# CAN0.net
KiCad netlist of a schematic drawn in Altium Designer
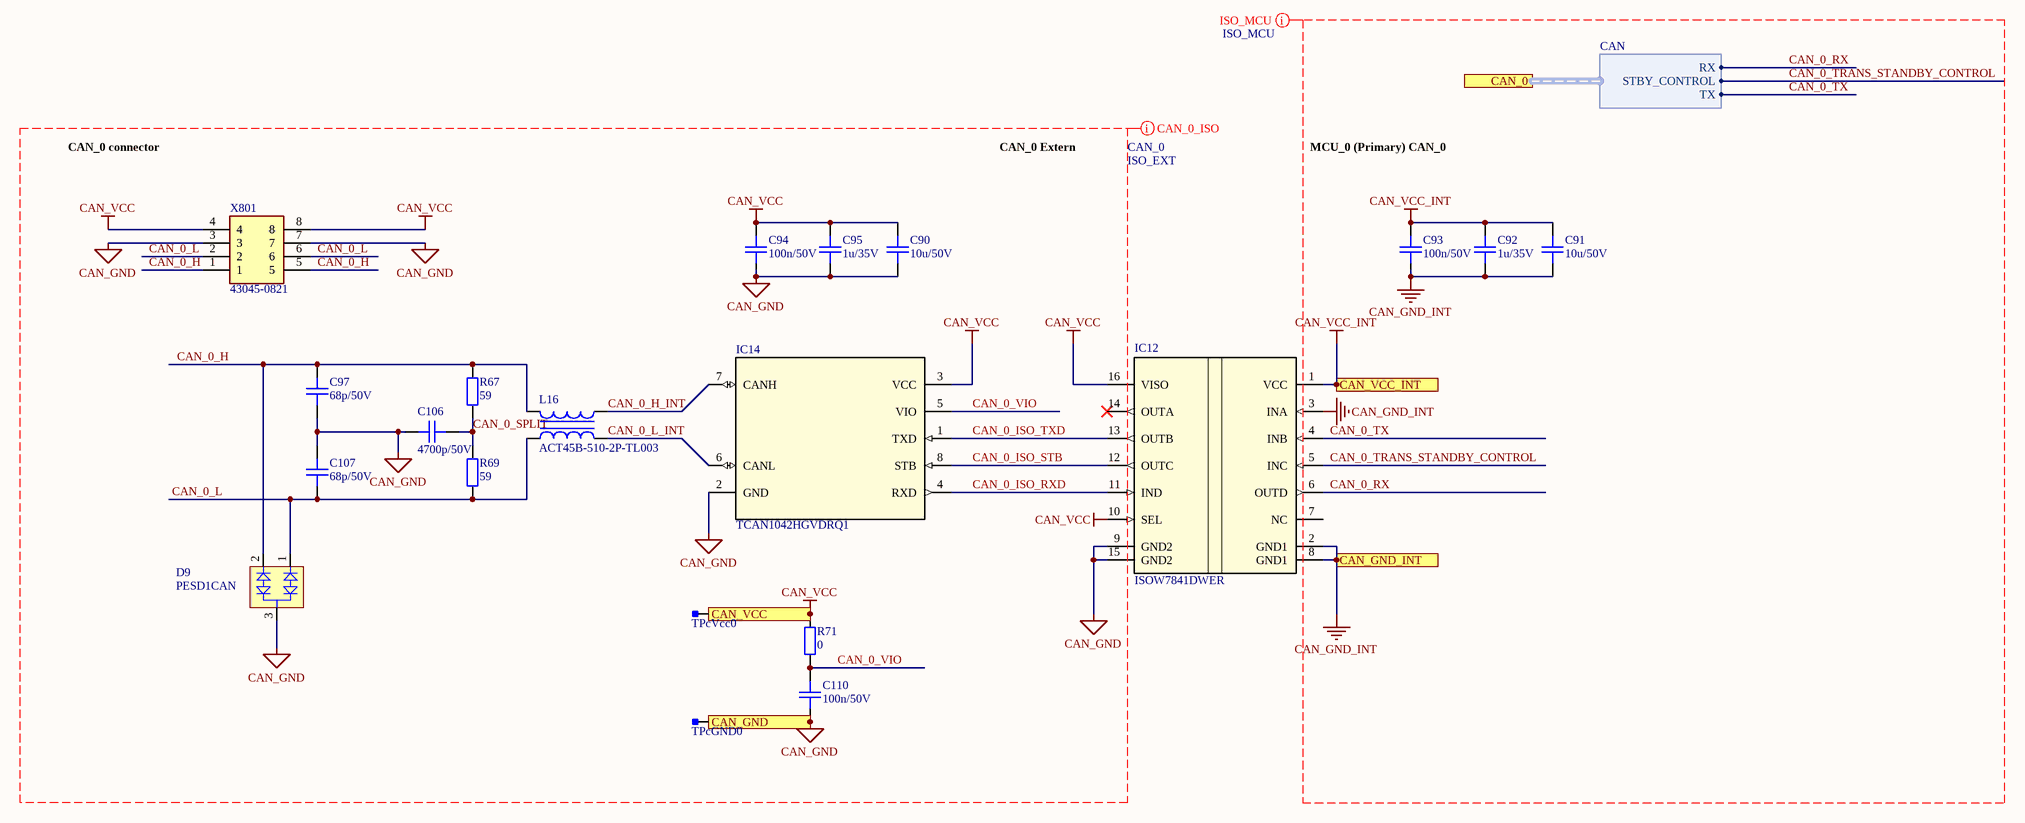
[diagram p0: CAN0.SchDoc]

(export (version "E")
  (design (tool "Eeschema 10.0.6"))
  (components
    (comp (ref "C90")
      (value "10u/50V")
      (footprint "0805C")
      (description "MLCC")
      (fields (field (name "PART NUMBER") "gen_C_ceramic_2u2_50V_X7R_0805"))
      (libsource (lib "OE750") (part "C"))
    )
    (comp (ref "C91")
      (value "10u/50V")
      (footprint "0805C")
      (description "MLCC")
      (fields (field (name "PART NUMBER") "gen_C_ceramic_2u2_50V_X7R_0805"))
      (libsource (lib "OE750") (part "C"))
    )
    (comp (ref "C92")
      (value "1u/35V")
      (footprint "0603C")
      (description "MLCC")
      (fields (field (name "PART NUMBER") "gen_C_ceramic_1u_35V_X7R_0603"))
      (libsource (lib "OE750") (part "C"))
    )
    (comp (ref "C93")
      (value "100n/50V")
      (footprint "0603C")
      (description "MLCC")
      (fields (field (name "PART NUMBER") "gen_C_ceramic_100n_50V_X7R_0603"))
      (libsource (lib "OE750") (part "C"))
    )
    (comp (ref "C94")
      (value "100n/50V")
      (footprint "0603C")
      (description "MLCC")
      (fields (field (name "PART NUMBER") "gen_C_ceramic_100n_50V_X7R_0603"))
      (libsource (lib "OE750") (part "C"))
    )
    (comp (ref "C95")
      (value "1u/35V")
      (footprint "0603C")
      (description "MLCC")
      (fields (field (name "PART NUMBER") "gen_C_ceramic_1u_35V_X7R_0603"))
      (libsource (lib "OE750") (part "C"))
    )
    (comp (ref "C97")
      (value "68p/50V")
      (footprint "0603C")
      (description "MLCC")
      (fields (field (name "PART NUMBER") "gen_C_ceramic_4n7_50V_X7R_0603"))
      (libsource (lib "OE750") (part "C"))
    )
    (comp (ref "C106")
      (value "4700p/50V")
      (footprint "0603C")
      (description "MLCC")
      (libsource (lib "OE750") (part "C"))
    )
    (comp (ref "C107")
      (value "68p/50V")
      (footprint "0603C")
      (description "MLCC")
      (fields (field (name "PART NUMBER") "gen_C_ceramic_4n7_50V_X7R_0603"))
      (libsource (lib "OE750") (part "C"))
    )
    (comp (ref "C110")
      (value "100n/50V")
      (footprint "0603C")
      (description "MLCC")
      (fields (field (name "PART NUMBER") "gen_C_ceramic_100n_50V_X7R_0603"))
      (libsource (lib "OE750") (part "C"))
    )
    (comp (ref "D9")
      (value "PESD1CAN")
      (footprint "NXP-SOT23-3_V")
      (description "CAN Bus ESD Protection Diode, 200 W, 24 V, -65 to 150 degC, 3-Pin SOT23, RoHS, Tape and Reel")
      (fields (field (name "MANUFACTURER") "NXP Semiconductors"))
      (libsource (lib "Altium Content Vault") (part "NXP-PESD1CAN-SOT23-3"))
    )
    (comp (ref "IC12")
      (value "ISOW7841DWER")
      (footprint "DWE0016A")
      (description "Imported")
      (fields (field (name "MANUFACTURER") "Texas Instruments"))
      (libsource (lib "ti-import") (part "ISOW7841DWER"))
    )
    (comp (ref "IC14")
      (value "TCAN1042HGVDRQ1")
      (footprint "D0008A_N")
      (description "Imported")
      (fields (field (name "PARTNUMBER") "TCAN1042HGVDQ1") (field (name "MANUFACTURER") "Texas Instruments"))
      (libsource (lib "ti-import") (part "TCAN1042HGVDRQ1"))
    )
    (comp (ref "L16")
      (value "ACT45B-510-2P-TL003")
      (footprint "TDK-ACT45B-510-2P-TL003-4_V")
      (fields (field (name "MANUFACTURER") "TDK"))
      (libsource (lib "Altium Content Vault") (part "TDK-ACXXXXX-XXX-2P-T000-4"))
    )
    (comp (ref "R67")
      (value "59")
      (footprint "0805R")
      (description "SMD Resistor 62R 0603")
      (fields (field (name "PART NUMBER") "gen_R_62R_0603") (field (name "TOLERANCE") "1%"))
      (libsource (lib "OE750") (part "R"))
    )
    (comp (ref "R69")
      (value "59")
      (footprint "0805R")
      (description "SMD Resistor 62R 0603")
      (fields (field (name "PART NUMBER") "gen_R_62R_0603") (field (name "TOLERANCE") "1%"))
      (libsource (lib "OE750") (part "R"))
    )
    (comp (ref "R71")
      (value "0")
      (footprint "0603R")
      (description "SMD Resistor 430R 0603")
      (fields (field (name "PART NUMBER") "gen_R_430R_0603") (field (name "TOLERANCE") "1%"))
      (libsource (lib "OE750") (part "R"))
    )
    (comp (ref "TPcGND0")
      (value "Testpoint_Square")
      (footprint "Testpoint_S1")
      (description "Testpoint, square")
      (libsource (lib "OE750") (part "Testpoint_Square"))
    )
    (comp (ref "TPcVcc0")
      (value "Testpoint_Square")
      (footprint "Testpoint_S1")
      (description "Testpoint, square")
      (libsource (lib "OE750") (part "Testpoint_Square"))
    )
    (comp (ref "X801")
      (value "43045-0821")
      (footprint "43045-0821")
      (description "Connector")
      (fields (field (name "MOUSER PART NUMBER") "538-43045-0821"))
      (libsource (lib "SamacSys") (part "43045-0821"))
    )
  )
  (nets
    (net (code "2") (name "/CAN_0_H") (class "Default")
      (node (ref "C97") (pin "2") (pinfunction "2_2") (pintype "passive"))
      (node (ref "D9") (pin "2") (pinfunction "K2_2") (pintype "passive"))
      (node (ref "L16") (pin "2") (pinfunction "2_2") (pintype "passive"))
      (node (ref "R67") (pin "2") (pinfunction "2_2") (pintype "passive"))
      (node (ref "X801") (pin "1") (pinfunction "1_1") (pintype "passive"))
      (node (ref "X801") (pin "5") (pinfunction "5_5") (pintype "passive"))
    )
    (net (code "3") (name "/CAN_0_H_INT") (class "Default")
      (node (ref "IC14") (pin "7") (pinfunction "CANH_7") (pintype "bidirectional"))
      (node (ref "L16") (pin "3") (pinfunction "3_3") (pintype "passive"))
    )
    (net (code "4") (name "/CAN_0_ISO_RXD") (class "Default")
      (node (ref "IC12") (pin "11") (pinfunction "IND_11") (pintype "input"))
      (node (ref "IC14") (pin "4") (pinfunction "RXD_4") (pintype "output"))
    )
    (net (code "5") (name "/CAN_0_ISO_STB") (class "Default")
      (node (ref "IC12") (pin "12") (pinfunction "OUTC_12") (pintype "output"))
      (node (ref "IC14") (pin "8") (pinfunction "STB_8") (pintype "input"))
    )
    (net (code "6") (name "/CAN_0_ISO_TXD") (class "Default")
      (node (ref "IC12") (pin "13") (pinfunction "OUTB_13") (pintype "output"))
      (node (ref "IC14") (pin "1") (pinfunction "TXD_1") (pintype "input"))
    )
    (net (code "7") (name "/CAN_0_L") (class "Default")
      (node (ref "C107") (pin "1") (pinfunction "1_1") (pintype "passive"))
      (node (ref "D9") (pin "1") (pinfunction "K1_1") (pintype "passive"))
      (node (ref "L16") (pin "1") (pinfunction "1_1") (pintype "passive"))
      (node (ref "R69") (pin "1") (pinfunction "1_1") (pintype "passive"))
      (node (ref "X801") (pin "2") (pinfunction "2_2") (pintype "passive"))
      (node (ref "X801") (pin "6") (pinfunction "6_6") (pintype "passive"))
    )
    (net (code "8") (name "/CAN_0_L_INT") (class "Default")
      (node (ref "IC14") (pin "6") (pinfunction "CANL_6") (pintype "bidirectional"))
      (node (ref "L16") (pin "4") (pinfunction "4_4") (pintype "passive"))
    )
    (net (code "9") (name "/CAN_0_RX") (class "Default")
      (node (ref "IC12") (pin "6") (pinfunction "OUTD_6") (pintype "output"))
    )
    (net (code "10") (name "/CAN_0_SPLIT") (class "Default")
      (node (ref "C106") (pin "2") (pinfunction "2_2") (pintype "passive"))
      (node (ref "R67") (pin "1") (pinfunction "1_1") (pintype "passive"))
      (node (ref "R69") (pin "2") (pinfunction "2_2") (pintype "passive"))
    )
    (net (code "11") (name "/CAN_0_TRANS_STANDBY_CONTROL") (class "Default")
      (node (ref "IC12") (pin "5") (pinfunction "INC_5") (pintype "input"))
    )
    (net (code "12") (name "/CAN_0_TX") (class "Default")
      (node (ref "IC12") (pin "4") (pinfunction "INB_4") (pintype "input"))
    )
    (net (code "13") (name "/CAN_0_VIO") (class "Default")
      (node (ref "C110") (pin "2") (pinfunction "2_2") (pintype "passive"))
      (node (ref "IC14") (pin "5") (pinfunction "VIO_5") (pintype "power_in"))
      (node (ref "R71") (pin "2") (pinfunction "2_2") (pintype "passive"))
    )
    (net (code "15") (name "CAN_GND") (class "Default")
      (node (ref "C106") (pin "1") (pinfunction "1_1") (pintype "passive"))
      (node (ref "C107") (pin "2") (pinfunction "2_2") (pintype "passive"))
      (node (ref "C110") (pin "1") (pinfunction "1_1") (pintype "passive"))
      (node (ref "C90") (pin "2") (pinfunction "2_2") (pintype "passive"))
      (node (ref "C94") (pin "1") (pinfunction "1_1") (pintype "passive"))
      (node (ref "C95") (pin "1") (pinfunction "1_1") (pintype "passive"))
      (node (ref "C97") (pin "1") (pinfunction "1_1") (pintype "passive"))
      (node (ref "D9") (pin "3") (pinfunction "C_3") (pintype "passive"))
      (node (ref "IC12") (pin "15") (pinfunction "GND2_15") (pintype "power_in"))
      (node (ref "IC12") (pin "9") (pinfunction "GND2_9") (pintype "power_in"))
      (node (ref "IC14") (pin "2") (pinfunction "GND_2") (pintype "power_in"))
      (node (ref "TPcGND0") (pin "1") (pinfunction "1_1") (pintype "passive"))
      (node (ref "X801") (pin "3") (pinfunction "3_3") (pintype "passive"))
      (node (ref "X801") (pin "7") (pinfunction "7_7") (pintype "passive"))
    )
    (net (code "16") (name "CAN_GND_INT") (class "Default")
      (node (ref "C91") (pin "2") (pinfunction "2_2") (pintype "passive"))
      (node (ref "C92") (pin "1") (pinfunction "1_1") (pintype "passive"))
      (node (ref "C93") (pin "1") (pinfunction "1_1") (pintype "passive"))
      (node (ref "IC12") (pin "2") (pinfunction "GND1_2") (pintype "power_in"))
      (node (ref "IC12") (pin "3") (pinfunction "INA_3") (pintype "input"))
      (node (ref "IC12") (pin "8") (pinfunction "GND1_8") (pintype "power_in"))
    )
    (net (code "17") (name "CAN_VCC") (class "Default")
      (node (ref "C90") (pin "1") (pinfunction "1_1") (pintype "passive"))
      (node (ref "C94") (pin "2") (pinfunction "2_2") (pintype "passive"))
      (node (ref "C95") (pin "2") (pinfunction "2_2") (pintype "passive"))
      (node (ref "IC12") (pin "10") (pinfunction "SEL_10") (pintype "input"))
      (node (ref "IC12") (pin "16") (pinfunction "VISO_16") (pintype "power_in"))
      (node (ref "IC14") (pin "3") (pinfunction "VCC_3") (pintype "power_in"))
      (node (ref "R71") (pin "1") (pinfunction "1_1") (pintype "passive"))
      (node (ref "TPcVcc0") (pin "1") (pinfunction "1_1") (pintype "passive"))
      (node (ref "X801") (pin "4") (pinfunction "4_4") (pintype "passive"))
      (node (ref "X801") (pin "8") (pinfunction "8_8") (pintype "passive"))
    )
    (net (code "18") (name "CAN_VCC_INT") (class "Default")
      (node (ref "C91") (pin "1") (pinfunction "1_1") (pintype "passive"))
      (node (ref "C92") (pin "2") (pinfunction "2_2") (pintype "passive"))
      (node (ref "C93") (pin "2") (pinfunction "2_2") (pintype "passive"))
      (node (ref "IC12") (pin "1") (pinfunction "VCC_1") (pintype "power_in"))
    )
    (net (code "19") (name "unconnected-(IC12-NC-Pad7)") (class "Default")
      (node (ref "IC12") (pin "7") (pinfunction "NC_7") (pintype "passive"))
    )
    (net (code "20") (name "unconnected-(IC12-OUTA-Pad14)") (class "Default")
      (node (ref "IC12") (pin "14") (pinfunction "OUTA_14") (pintype "output+no_connect"))
    )
  )
)
